# Power_Distribution_Board_Task_6.net
KiCad netlist of a schematic drawn in EAGLE
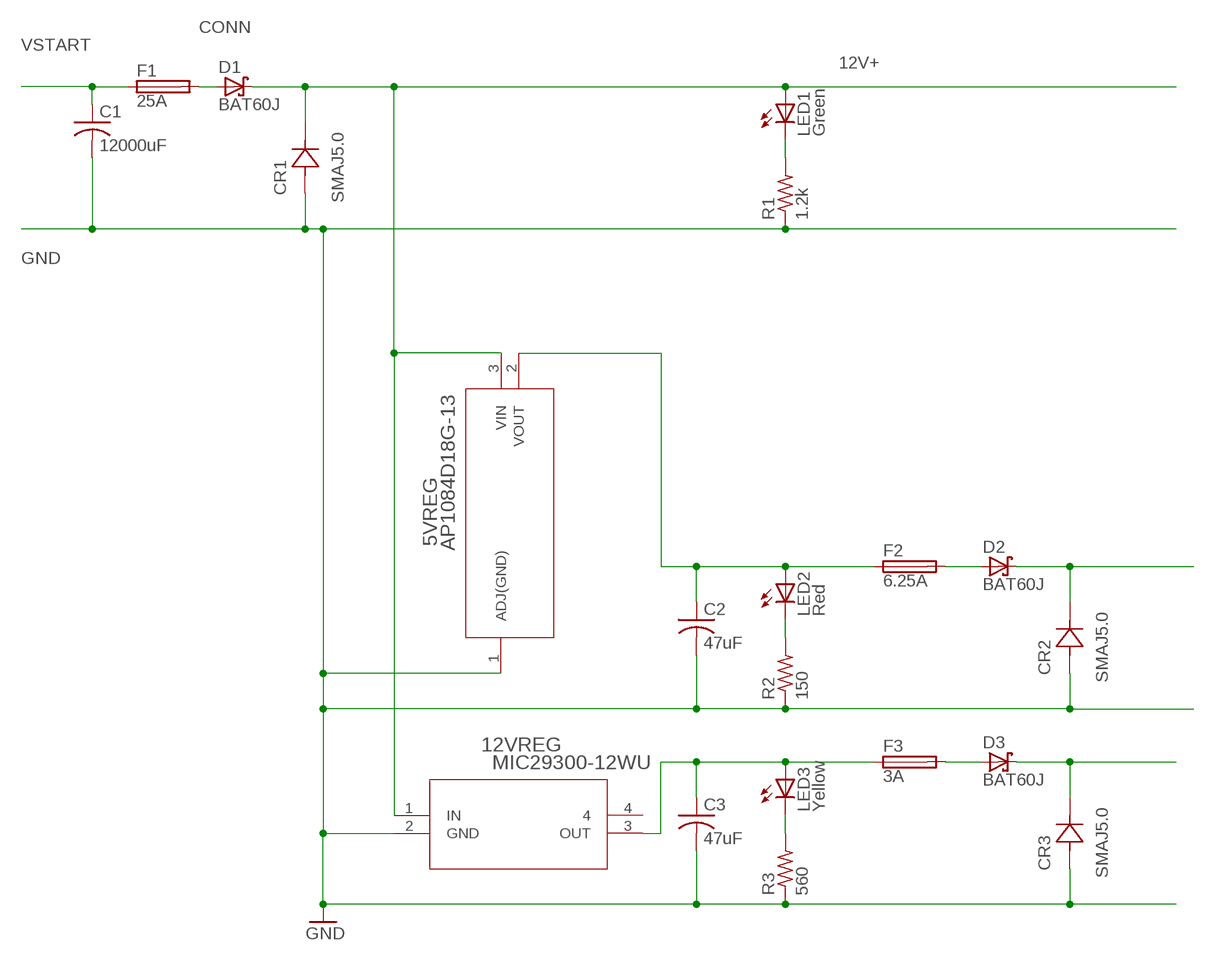
[diagram p0: schematic, sheet 1]

(export (version "E")
  (design (tool "Eeschema 10.0.6"))
  (components
    (comp (ref "5VREG")
      (value "AP1084D18G-13")
      (footprint "eagle-import:TO252-3L")
      (fields (field (name "MANUFACTURER_PART_NUMBER") "AP1084D18G13"))
      (libsource (lib "eagle-import") (part "AP1084D18G-13"))
    )
    (comp (ref "12VREG")
      (value "MIC29300-12WU")
      (footprint "eagle-import:TO-263-3")
      (fields (field (name "MANUFACTURER_PART_NUMBER") "MIC2930012WU"))
      (libsource (lib "eagle-import") (part "MIC29300-12WU"))
    )
    (comp (ref "C1")
      (value "12000uF")
      (footprint "eagle-import:C1206K")
      (libsource (lib "eagle-import") (part "C-USC1206K"))
    )
    (comp (ref "C2")
      (value "47uF")
      (footprint "eagle-import:C1206K")
      (libsource (lib "eagle-import") (part "C-USC1206K"))
    )
    (comp (ref "C3")
      (value "47uF")
      (footprint "eagle-import:C1206K")
      (libsource (lib "eagle-import") (part "C-USC1206K"))
    )
    (comp (ref "CR1")
      (value "SMAJ5.0")
      (footprint "eagle-import:SMASERIES")
      (libsource (lib "eagle-import") (part "SMAJ5.0"))
    )
    (comp (ref "CR2")
      (value "SMAJ5.0")
      (footprint "eagle-import:SMASERIES")
      (libsource (lib "eagle-import") (part "SMAJ5.0"))
    )
    (comp (ref "CR3")
      (value "SMAJ5.0")
      (footprint "eagle-import:SMASERIES")
      (libsource (lib "eagle-import") (part "SMAJ5.0"))
    )
    (comp (ref "D1")
      (value "BAT60J")
      (footprint "eagle-import:SOD323_ST")
      (libsource (lib "eagle-import") (part "BAT60J"))
    )
    (comp (ref "D2")
      (value "BAT60J")
      (footprint "eagle-import:SOD323_ST")
      (libsource (lib "eagle-import") (part "BAT60J"))
    )
    (comp (ref "D3")
      (value "BAT60J")
      (footprint "eagle-import:SOD323_ST")
      (libsource (lib "eagle-import") (part "BAT60J"))
    )
    (comp (ref "F1")
      (value "25A")
      (footprint "eagle-import:TE5")
      (libsource (lib "eagle-import") (part "TE5"))
    )
    (comp (ref "F2")
      (value "6.25A")
      (footprint "eagle-import:TE5")
      (libsource (lib "eagle-import") (part "TE5"))
    )
    (comp (ref "F3")
      (value "3A")
      (footprint "eagle-import:TE5")
      (libsource (lib "eagle-import") (part "TE5"))
    )
    (comp (ref "LED1")
      (value "Green")
      (footprint "eagle-import:CHIPLED_1206")
      (libsource (lib "eagle-import") (part "LEDCHIPLED_1206"))
    )
    (comp (ref "LED2")
      (value "Red")
      (footprint "eagle-import:CHIPLED_1206")
      (libsource (lib "eagle-import") (part "LEDCHIPLED_1206"))
    )
    (comp (ref "LED3")
      (value "Yellow")
      (footprint "eagle-import:CHIPLED_1206")
      (libsource (lib "eagle-import") (part "LEDCHIPLED_1206"))
    )
    (comp (ref "R1")
      (value "1.2k")
      (footprint "eagle-import:R1206")
      (libsource (lib "eagle-import") (part "R-US_R1206"))
    )
    (comp (ref "R2")
      (value "150")
      (footprint "eagle-import:R1206")
      (libsource (lib "eagle-import") (part "R-US_R1206"))
    )
    (comp (ref "R3")
      (value "560")
      (footprint "eagle-import:R1206")
      (libsource (lib "eagle-import") (part "R-US_R1206"))
    )
  )
  (nets
    (net (code "1") (name "/12V+") (class "Default")
      (node (ref "12VREG") (pin "1") (pinfunction "IN_1") (pintype "input"))
      (node (ref "5VREG") (pin "3") (pinfunction "VIN_3") (pintype "input"))
      (node (ref "CR1") (pin "1") (pinfunction "2_1") (pintype "passive"))
      (node (ref "D1") (pin "C") (pinfunction "C_C") (pintype "passive"))
      (node (ref "LED1") (pin "A") (pinfunction "A_A") (pintype "passive"))
    )
    (net (code "2") (name "/CONN") (class "Default")
      (node (ref "D1") (pin "A") (pinfunction "A_A") (pintype "passive"))
      (node (ref "F1") (pin "2") (pinfunction "2_2") (pintype "passive"))
    )
    (net (code "3") (name "/VSTART") (class "Default")
      (node (ref "C1") (pin "1") (pinfunction "1_1") (pintype "passive"))
      (node (ref "F1") (pin "1") (pinfunction "1_1") (pintype "passive"))
    )
    (net (code "4") (name "GND") (class "Default")
      (node (ref "12VREG") (pin "2") (pinfunction "GND_2") (pintype "power_in"))
      (node (ref "5VREG") (pin "1") (pinfunction "ADJ(GND)_1") (pintype "passive"))
      (node (ref "C1") (pin "2") (pinfunction "2_2") (pintype "passive"))
      (node (ref "C2") (pin "2") (pinfunction "2_2") (pintype "passive"))
      (node (ref "C3") (pin "2") (pinfunction "2_2") (pintype "passive"))
      (node (ref "CR1") (pin "2") (pinfunction "1_2") (pintype "passive"))
      (node (ref "CR2") (pin "2") (pinfunction "1_2") (pintype "passive"))
      (node (ref "CR3") (pin "2") (pinfunction "1_2") (pintype "passive"))
      (node (ref "R1") (pin "1") (pinfunction "1_1") (pintype "passive"))
      (node (ref "R2") (pin "1") (pinfunction "1_1") (pintype "passive"))
      (node (ref "R3") (pin "1") (pinfunction "1_1") (pintype "passive"))
    )
    (net (code "5") (name "Net-(5VREG-VOUT)") (class "Default")
      (node (ref "5VREG") (pin "2") (pinfunction "VOUT_2") (pintype "output"))
      (node (ref "C2") (pin "1") (pinfunction "1_1") (pintype "passive"))
      (node (ref "F2") (pin "1") (pinfunction "1_1") (pintype "passive"))
      (node (ref "LED2") (pin "A") (pinfunction "A_A") (pintype "passive"))
    )
    (net (code "6") (name "Net-(12VREG-OUT)") (class "Default")
      (node (ref "12VREG") (pin "3") (pinfunction "OUT_3") (pintype "output"))
      (node (ref "C3") (pin "1") (pinfunction "1_1") (pintype "passive"))
      (node (ref "F3") (pin "1") (pinfunction "1_1") (pintype "passive"))
      (node (ref "LED3") (pin "A") (pinfunction "A_A") (pintype "passive"))
    )
    (net (code "7") (name "Net-(CR2-2)") (class "Default")
      (node (ref "CR2") (pin "1") (pinfunction "2_1") (pintype "passive"))
      (node (ref "D2") (pin "C") (pinfunction "C_C") (pintype "passive"))
    )
    (net (code "8") (name "Net-(CR3-2)") (class "Default")
      (node (ref "CR3") (pin "1") (pinfunction "2_1") (pintype "passive"))
      (node (ref "D3") (pin "C") (pinfunction "C_C") (pintype "passive"))
    )
    (net (code "9") (name "Net-(D2-PadA)") (class "Default")
      (node (ref "D2") (pin "A") (pinfunction "A_A") (pintype "passive"))
      (node (ref "F2") (pin "2") (pinfunction "2_2") (pintype "passive"))
    )
    (net (code "10") (name "Net-(D3-PadA)") (class "Default")
      (node (ref "D3") (pin "A") (pinfunction "A_A") (pintype "passive"))
      (node (ref "F3") (pin "2") (pinfunction "2_2") (pintype "passive"))
    )
    (net (code "11") (name "Net-(LED1-PadC)") (class "Default")
      (node (ref "LED1") (pin "C") (pinfunction "C_C") (pintype "passive"))
      (node (ref "R1") (pin "2") (pinfunction "2_2") (pintype "passive"))
    )
    (net (code "12") (name "Net-(LED2-PadC)") (class "Default")
      (node (ref "LED2") (pin "C") (pinfunction "C_C") (pintype "passive"))
      (node (ref "R2") (pin "2") (pinfunction "2_2") (pintype "passive"))
    )
    (net (code "13") (name "Net-(LED3-PadC)") (class "Default")
      (node (ref "LED3") (pin "C") (pinfunction "C_C") (pintype "passive"))
      (node (ref "R3") (pin "2") (pinfunction "2_2") (pintype "passive"))
    )
    (net (code "14") (name "unconnected-(12VREG-Pad4)") (class "Default")
      (node (ref "12VREG") (pin "4") (pinfunction "4_4") (pintype "passive"))
    )
  )
)
